# L240-1.net
KiCad netlist of a schematic drawn in EAGLE
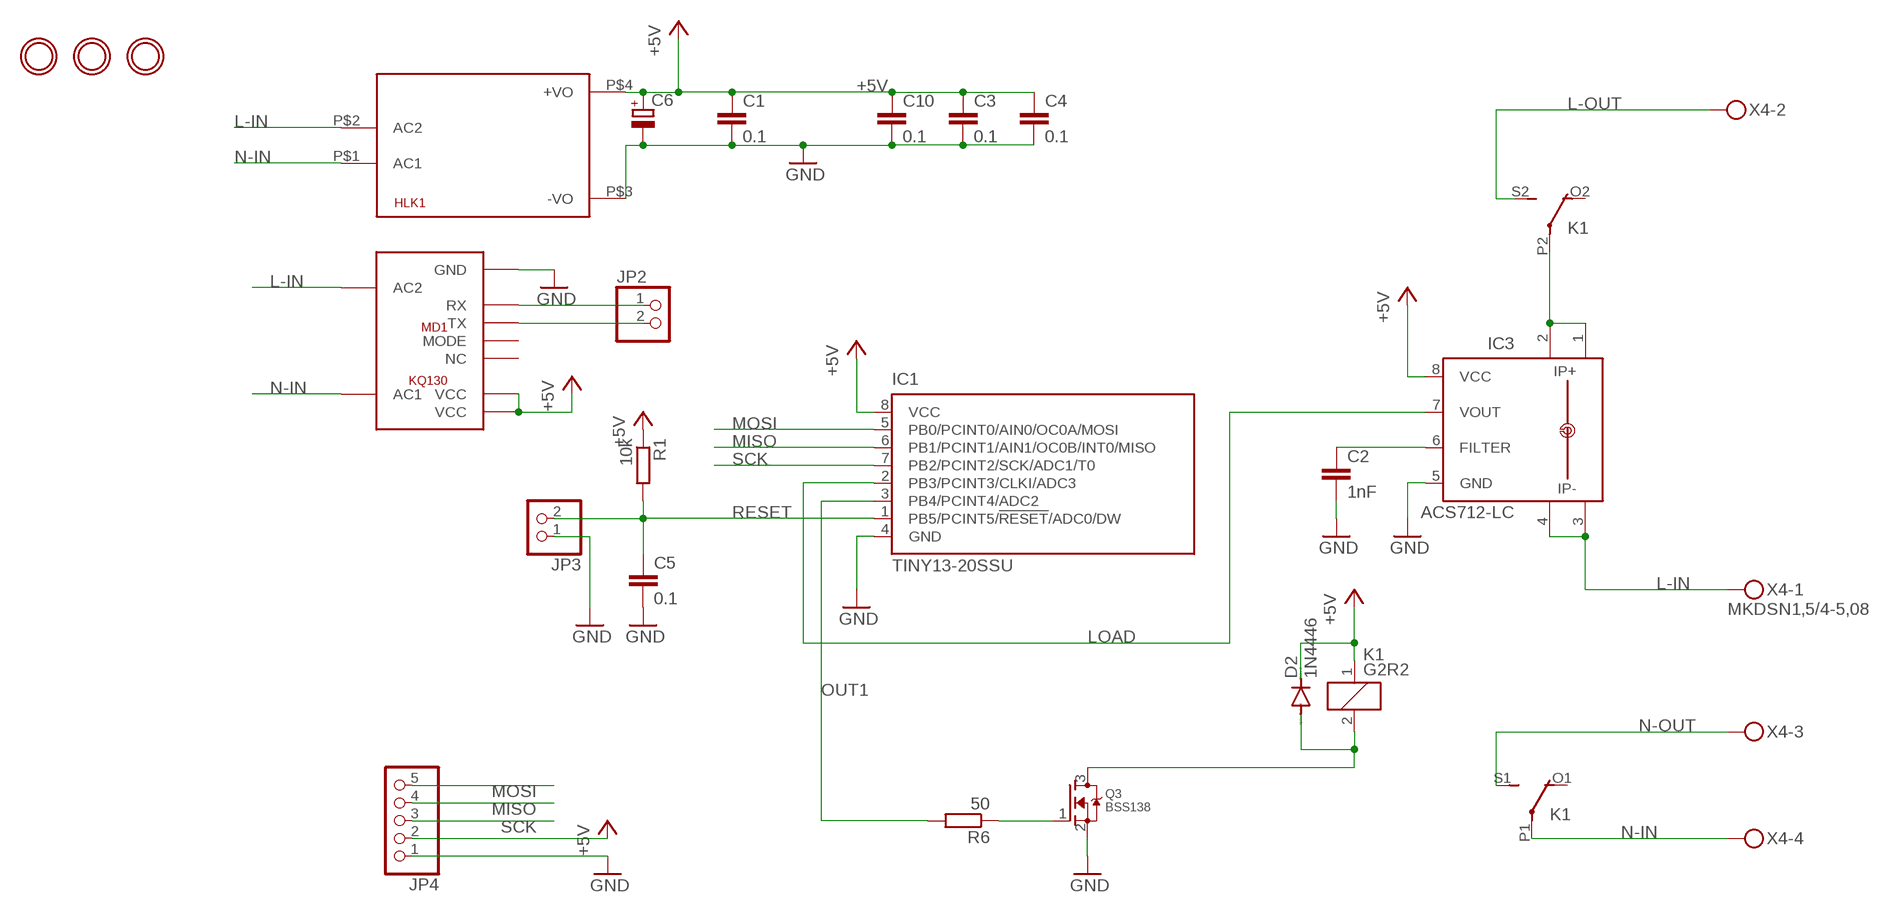
[diagram p0: schematic, sheet 1]

(export (version "E")
  (design (tool "Eeschema 10.0.6"))
  (components
    (comp (ref "C1")
      (value "0.1")
      (footprint "eagle-import:C0805")
      (libsource (lib "eagle-import") (part "C-EUC0805"))
    )
    (comp (ref "C2")
      (value "1nF")
      (footprint "eagle-import:C0805")
      (libsource (lib "eagle-import") (part "C-EUC0805"))
    )
    (comp (ref "C3")
      (value "0.1")
      (footprint "eagle-import:C0805")
      (libsource (lib "eagle-import") (part "C-EUC0805"))
    )
    (comp (ref "C4")
      (value "0.1")
      (footprint "eagle-import:C0805")
      (libsource (lib "eagle-import") (part "C-EUC0805"))
    )
    (comp (ref "C5")
      (value "0.1")
      (footprint "eagle-import:C0805")
      (libsource (lib "eagle-import") (part "C-EUC0805"))
    )
    (comp (ref "C6")
      (value "CPOL-EUE5-5")
      (footprint "eagle-import:E5-5")
      (libsource (lib "eagle-import") (part "CPOL-EUE5-5"))
    )
    (comp (ref "C10")
      (value "0.1")
      (footprint "eagle-import:C0805")
      (libsource (lib "eagle-import") (part "C-EUC0805"))
    )
    (comp (ref "D2")
      (value "1N4446")
      (footprint "eagle-import:DO35-10")
      (libsource (lib "eagle-import") (part "1N4446"))
    )
    (comp (ref "HLK1")
      (value "HLK-PM013W")
      (footprint "eagle-import:HLK-PM01")
      (libsource (lib "eagle-import") (part "HLK-PM013W"))
    )
    (comp (ref "IC1")
      (value "TINY13-20SSU")
      (footprint "eagle-import:8S1")
      (fields (field (name "MPN") "ATTINY13-20SSU"))
      (libsource (lib "eagle-import") (part "TINY13SSU-20"))
    )
    (comp (ref "IC3")
      (value "ACS712-LC")
      (footprint "eagle-import:SOIC8")
      (libsource (lib "eagle-import") (part "ACS712-LC"))
    )
    (comp (ref "JP2")
      (value "PINHD-1X2")
      (footprint "eagle-import:1X02")
      (libsource (lib "eagle-import") (part "PINHD-1X2"))
    )
    (comp (ref "JP3")
      (value "PINHD-1X2")
      (footprint "eagle-import:1X02")
      (libsource (lib "eagle-import") (part "PINHD-1X2"))
    )
    (comp (ref "JP4")
      (value "PINHD-1X5")
      (footprint "eagle-import:1X05")
      (libsource (lib "eagle-import") (part "PINHD-1X5"))
    )
    (comp (ref "K1")
      (value "G2R2")
      (footprint "eagle-import:G2R2")
      (fields (field (name "MF") "OMRON COMPONENTS USA") (field (name "MPN") "G2R-2-DC6"))
      (libsource (lib "eagle-import") (part "G2R2"))
    )
    (comp (ref "MD1")
      (value "KQ130")
      (footprint "eagle-import:KQ130")
      (libsource (lib "eagle-import") (part "KQ130"))
    )
    (comp (ref "Q3")
      (value "BSS138")
      (footprint "eagle-import:SOT23-WIDE")
      (libsource (lib "eagle-import") (part "MOSFET-NWIDE"))
    )
    (comp (ref "R1")
      (value "10k")
      (footprint "eagle-import:R0805")
      (libsource (lib "eagle-import") (part "R-EU_R0805"))
    )
    (comp (ref "R6")
      (value "50")
      (footprint "eagle-import:R0805")
      (libsource (lib "eagle-import") (part "R-EU_R0805"))
    )
    (comp (ref "U$1")
      (value "MOUNTINGHOLE3.0THIN")
      (footprint "eagle-import:MOUNTINGHOLE_3.0_PLATEDTHIN")
      (libsource (lib "eagle-import") (part "MOUNTINGHOLE3.0THIN"))
    )
    (comp (ref "U$2")
      (value "MOUNTINGHOLE3.0THIN")
      (footprint "eagle-import:MOUNTINGHOLE_3.0_PLATEDTHIN")
      (libsource (lib "eagle-import") (part "MOUNTINGHOLE3.0THIN"))
    )
    (comp (ref "U$3")
      (value "MOUNTINGHOLE3.0THIN")
      (footprint "eagle-import:MOUNTINGHOLE_3.0_PLATEDTHIN")
      (libsource (lib "eagle-import") (part "MOUNTINGHOLE3.0THIN"))
    )
    (comp (ref "X4")
      (value "MKDSN1,5/4-5,08")
      (footprint "eagle-import:MKDSN1,5_4-5,08")
      (libsource (lib "eagle-import") (part "MKDSN1,5/4-5,08"))
    )
  )
  (nets
    (net (code "1") (name "+5V") (class "Default")
      (node (ref "C1") (pin "1") (pinfunction "1_1") (pintype "passive"))
      (node (ref "C10") (pin "1") (pinfunction "1_1") (pintype "passive"))
      (node (ref "C3") (pin "1") (pinfunction "1_1") (pintype "passive"))
      (node (ref "C4") (pin "1") (pinfunction "1_1") (pintype "passive"))
      (node (ref "C6") (pin "+") (pinfunction "+_+") (pintype "passive"))
      (node (ref "D2") (pin "C") (pinfunction "C_C") (pintype "passive"))
      (node (ref "HLK1") (pin "P$4") (pinfunction "+VO_P$4") (pintype "bidirectional"))
      (node (ref "IC1") (pin "8") (pinfunction "VCC_8") (pintype "power_in"))
      (node (ref "IC3") (pin "8") (pinfunction "VCC_8") (pintype "power_in"))
      (node (ref "JP4") (pin "2") (pinfunction "2_2") (pintype "passive"))
      (node (ref "K1") (pin "1") (pinfunction "1_1") (pintype "passive"))
      (node (ref "MD1") (pin "VCC@1") (pinfunction "VCC_VCC@1") (pintype "power_in"))
      (node (ref "MD1") (pin "VCC@2") (pinfunction "VCC_VCC@2") (pintype "power_in"))
      (node (ref "R1") (pin "1") (pinfunction "1_1") (pintype "passive"))
    )
    (net (code "2") (name "/L-IN") (class "Default")
      (node (ref "HLK1") (pin "P$2") (pinfunction "AC2_P$2") (pintype "bidirectional"))
      (node (ref "IC3") (pin "3") (pinfunction "IP-_3") (pintype "passive"))
      (node (ref "IC3") (pin "4") (pinfunction "IP-1_4") (pintype "passive"))
      (node (ref "MD1") (pin "AC2") (pinfunction "AC2_AC2") (pintype "bidirectional"))
      (node (ref "X4") (pin "1") (pinfunction "KL_1") (pintype "passive"))
    )
    (net (code "3") (name "/L-OUT") (class "Default")
      (node (ref "K1") (pin "S2") (pinfunction "S_S2") (pintype "passive"))
      (node (ref "X4") (pin "2") (pinfunction "KL_2") (pintype "passive"))
    )
    (net (code "4") (name "/LOAD") (class "Default")
      (node (ref "IC1") (pin "2") (pinfunction "PB3/PCINT3/CLKI/ADC3_2") (pintype "bidirectional"))
      (node (ref "IC3") (pin "7") (pinfunction "VOUT_7") (pintype "output"))
    )
    (net (code "5") (name "/MISO") (class "Default")
      (node (ref "IC1") (pin "6") (pinfunction "PB1/PCINT1/AIN1/OC0B/INT0/MISO_6") (pintype "bidirectional"))
      (node (ref "JP4") (pin "4") (pinfunction "4_4") (pintype "passive"))
    )
    (net (code "6") (name "/MOSI") (class "Default")
      (node (ref "IC1") (pin "5") (pinfunction "PB0/PCINT0/AIN0/OC0A/MOSI_5") (pintype "bidirectional"))
      (node (ref "JP4") (pin "5") (pinfunction "5_5") (pintype "passive"))
    )
    (net (code "7") (name "/N-IN") (class "Default")
      (node (ref "HLK1") (pin "P$1") (pinfunction "AC1_P$1") (pintype "bidirectional"))
      (node (ref "K1") (pin "P1") (pinfunction "P_P1") (pintype "passive"))
      (node (ref "MD1") (pin "AC1") (pinfunction "AC1_AC1") (pintype "bidirectional"))
      (node (ref "X4") (pin "4") (pinfunction "KL_4") (pintype "passive"))
    )
    (net (code "8") (name "/N-OUT") (class "Default")
      (node (ref "K1") (pin "S1") (pinfunction "S_S1") (pintype "passive"))
      (node (ref "X4") (pin "3") (pinfunction "KL_3") (pintype "passive"))
    )
    (net (code "9") (name "/OUT1") (class "Default")
      (node (ref "IC1") (pin "3") (pinfunction "PB4/PCINT4/ADC2_3") (pintype "bidirectional"))
      (node (ref "R6") (pin "2") (pinfunction "2_2") (pintype "passive"))
    )
    (net (code "10") (name "/RESET") (class "Default")
      (node (ref "C5") (pin "1") (pinfunction "1_1") (pintype "passive"))
      (node (ref "IC1") (pin "1") (pinfunction "PB5/PCINT5/~{RESET}/ADC0/DW_1") (pintype "bidirectional"))
      (node (ref "JP3") (pin "2") (pinfunction "2_2") (pintype "passive"))
      (node (ref "R1") (pin "2") (pinfunction "2_2") (pintype "passive"))
    )
    (net (code "11") (name "/SCK") (class "Default")
      (node (ref "IC1") (pin "7") (pinfunction "PB2/PCINT2/SCK/ADC1/T0_7") (pintype "bidirectional"))
      (node (ref "JP4") (pin "3") (pinfunction "3_3") (pintype "passive"))
    )
    (net (code "12") (name "GND") (class "Default")
      (node (ref "C1") (pin "2") (pinfunction "2_2") (pintype "passive"))
      (node (ref "C10") (pin "2") (pinfunction "2_2") (pintype "passive"))
      (node (ref "C2") (pin "2") (pinfunction "2_2") (pintype "passive"))
      (node (ref "C3") (pin "2") (pinfunction "2_2") (pintype "passive"))
      (node (ref "C4") (pin "2") (pinfunction "2_2") (pintype "passive"))
      (node (ref "C5") (pin "2") (pinfunction "2_2") (pintype "passive"))
      (node (ref "C6") (pin "-") (pinfunction "-_-") (pintype "passive"))
      (node (ref "HLK1") (pin "P$3") (pinfunction "-VO_P$3") (pintype "bidirectional"))
      (node (ref "IC1") (pin "4") (pinfunction "GND_4") (pintype "power_in"))
      (node (ref "IC3") (pin "5") (pinfunction "GND_5") (pintype "power_in"))
      (node (ref "JP3") (pin "1") (pinfunction "1_1") (pintype "passive"))
      (node (ref "JP4") (pin "1") (pinfunction "1_1") (pintype "passive"))
      (node (ref "MD1") (pin "GND") (pinfunction "GND_GND") (pintype "power_in"))
      (node (ref "Q3") (pin "2") (pinfunction "S_2") (pintype "bidirectional"))
    )
    (net (code "13") (name "Net-(IC3-FILTER)") (class "Default")
      (node (ref "C2") (pin "1") (pinfunction "1_1") (pintype "passive"))
      (node (ref "IC3") (pin "6") (pinfunction "FILTER_6") (pintype "bidirectional"))
    )
    (net (code "14") (name "Net-(IC3-IP+)") (class "Default")
      (node (ref "IC3") (pin "1") (pinfunction "IP+_1") (pintype "passive"))
      (node (ref "IC3") (pin "2") (pinfunction "IP+1_2") (pintype "passive"))
      (node (ref "K1") (pin "P2") (pinfunction "P_P2") (pintype "passive"))
    )
    (net (code "15") (name "Net-(JP2-Pad1)") (class "Default")
      (node (ref "JP2") (pin "1") (pinfunction "1_1") (pintype "passive"))
      (node (ref "MD1") (pin "RX") (pinfunction "RX_RX") (pintype "bidirectional"))
    )
    (net (code "16") (name "Net-(JP2-Pad2)") (class "Default")
      (node (ref "JP2") (pin "2") (pinfunction "2_2") (pintype "passive"))
      (node (ref "MD1") (pin "TX") (pinfunction "TX_TX") (pintype "bidirectional"))
    )
    (net (code "17") (name "Net-(Q3-D)") (class "Default")
      (node (ref "D2") (pin "A") (pinfunction "A_A") (pintype "passive"))
      (node (ref "K1") (pin "2") (pinfunction "2_2") (pintype "passive"))
      (node (ref "Q3") (pin "3") (pinfunction "D_3") (pintype "bidirectional"))
    )
    (net (code "18") (name "Net-(Q3-G)") (class "Default")
      (node (ref "Q3") (pin "1") (pinfunction "G_1") (pintype "bidirectional"))
      (node (ref "R6") (pin "1") (pinfunction "1_1") (pintype "passive"))
    )
    (net (code "19") (name "unconnected-(K1B-O-PadO1)") (class "Default")
      (node (ref "K1") (pin "O1") (pinfunction "O_O1") (pintype "passive"))
    )
    (net (code "20") (name "unconnected-(K1C-O-PadO2)") (class "Default")
      (node (ref "K1") (pin "O2") (pinfunction "O_O2") (pintype "passive"))
    )
    (net (code "21") (name "unconnected-(MD1-PadMODE)") (class "Default")
      (node (ref "MD1") (pin "MODE") (pinfunction "MODE_MODE") (pintype "input"))
    )
    (net (code "22") (name "unconnected-(MD1-PadNC)") (class "Default")
      (node (ref "MD1") (pin "NC") (pinfunction "NC_NC") (pintype "no_connect"))
    )
  )
)
